# HB-UNI-SEN-PHO.net
KiCad netlist of a schematic drawn in EAGLE
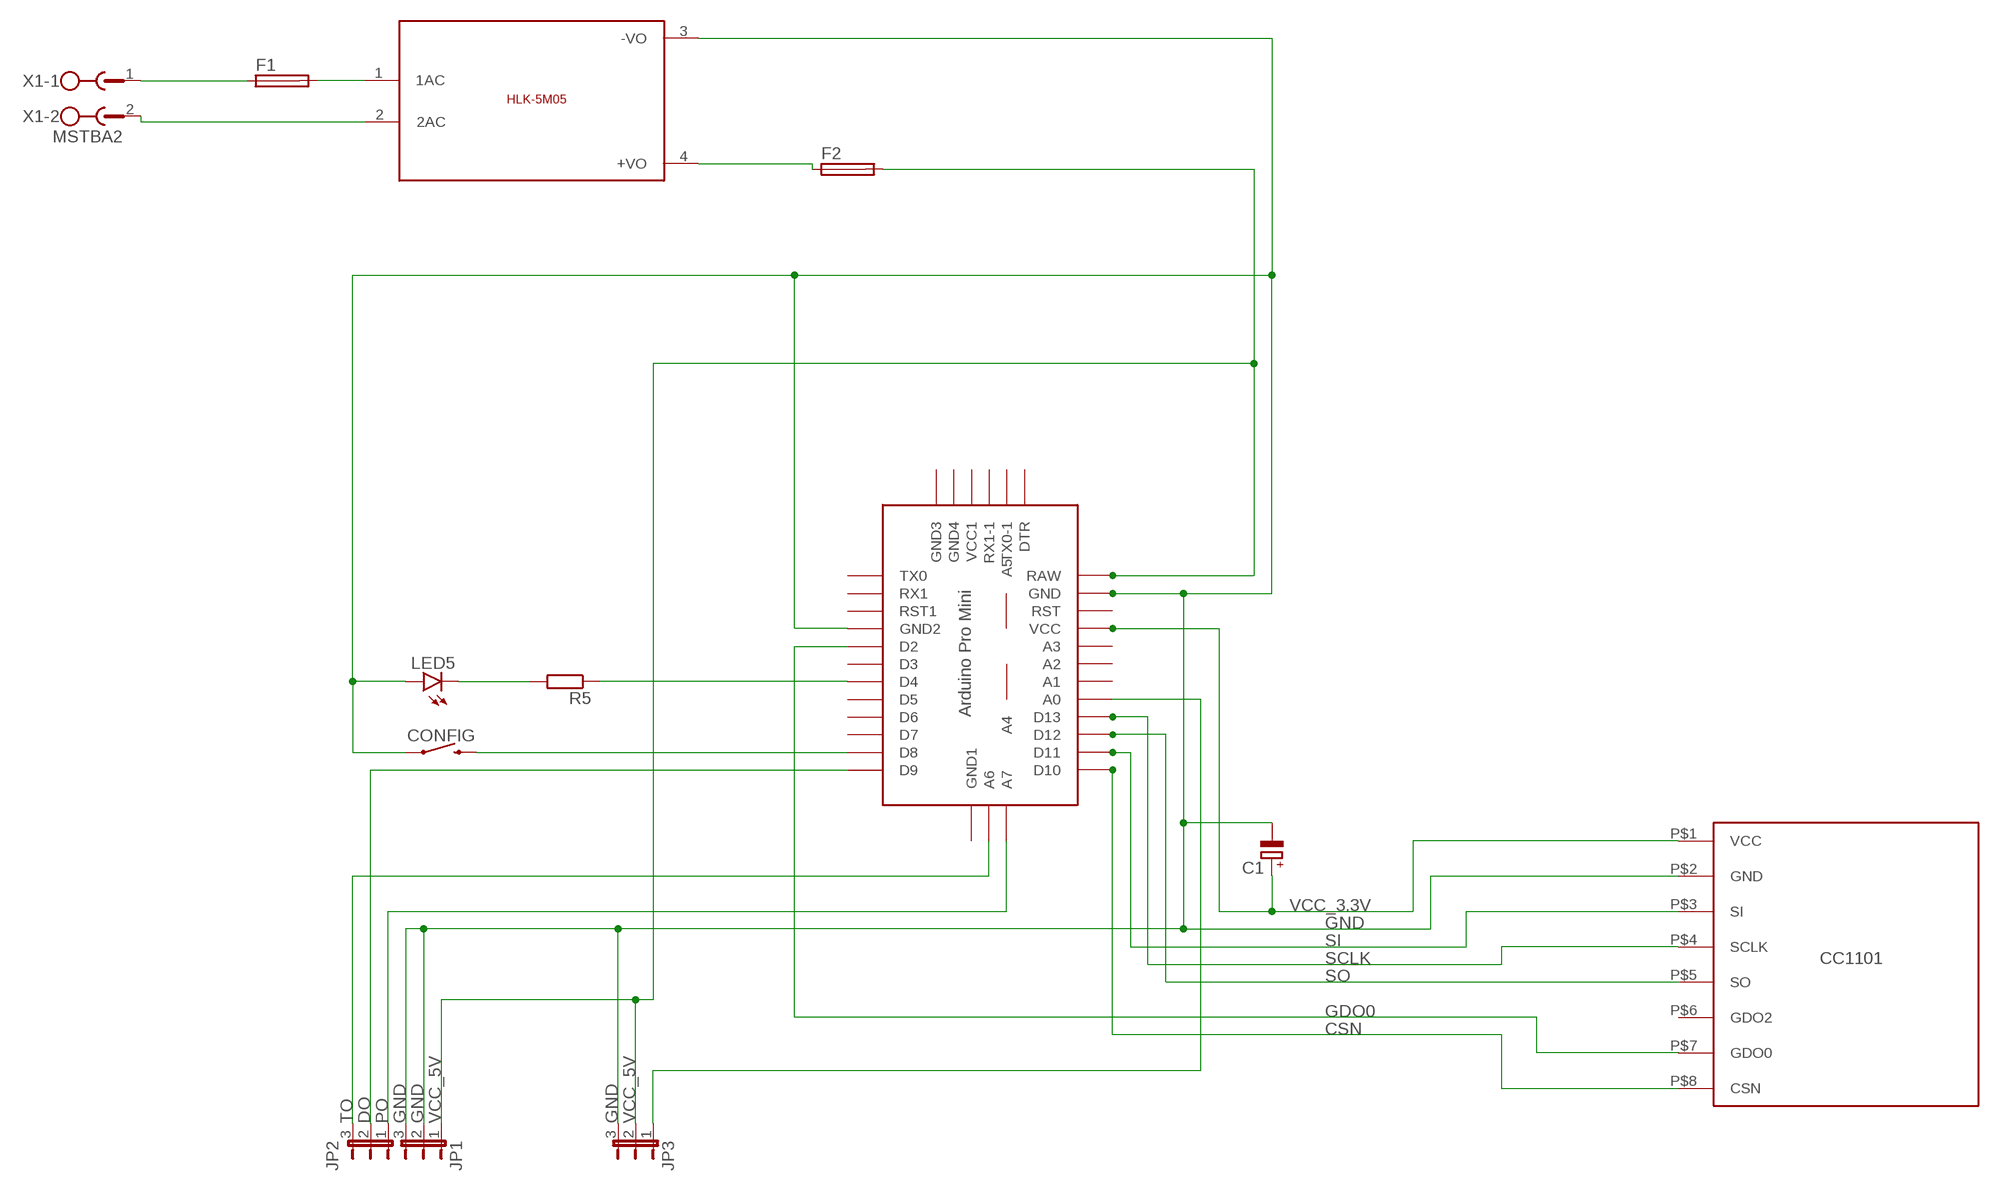
[diagram p0: schematic, sheet 1]

(export (version "E")
  (design (tool "Eeschema 10.0.6"))
  (components
    (comp (ref "C1")
      (value "CPOL-EUE2.5-5")
      (footprint "eagle-import:E2,5-5")
      (libsource (lib "eagle-import") (part "CPOL-EUE2.5-5"))
    )
    (comp (ref "CONFIG")
      (value "MOMENTARY-SWITCH-SPST-PTH-6.0MM-KIT")
      (footprint "eagle-import:TACTILE_SWITCH_PTH_6.0MM_KIT")
      (libsource (lib "eagle-import") (part "MOMENTARY-SWITCH-SPST-PTH-6.0MM-KIT"))
    )
    (comp (ref "F1")
      (value "SH22,5A")
      (footprint "eagle-import:SH22,5A")
      (fields (field (name "MPN") "0031.7701.11"))
      (libsource (lib "eagle-import") (part "SH22,5A"))
    )
    (comp (ref "F2")
      (value "SH22,5A")
      (footprint "eagle-import:SH22,5A")
      (fields (field (name "MPN") "0031.7701.11"))
      (libsource (lib "eagle-import") (part "SH22,5A"))
    )
    (comp (ref "JP1")
      (value "JP2E")
      (footprint "eagle-import:JP2")
      (libsource (lib "eagle-import") (part "JP2E"))
    )
    (comp (ref "JP2")
      (value "JP2E")
      (footprint "eagle-import:JP2")
      (libsource (lib "eagle-import") (part "JP2E"))
    )
    (comp (ref "JP3")
      (value "JP2E")
      (footprint "eagle-import:JP2")
      (libsource (lib "eagle-import") (part "JP2E"))
    )
    (comp (ref "LED5")
      (value "LED3MM")
      (footprint "eagle-import:LED3MM")
      (libsource (lib "eagle-import") (part "LED3MM"))
    )
    (comp (ref "R5")
      (value "R-EU_0309/10")
      (footprint "eagle-import:0309_10")
      (libsource (lib "eagle-import") (part "R-EU_0309/10"))
    )
    (comp (ref "U$2")
      (value "ABK-PRO-MINI")
      (footprint "eagle-import:ABK-PRO-MINI")
      (libsource (lib "eagle-import") (part "ABK-PRO-MINI"))
    )
    (comp (ref "U$3")
      (value "5VDC/5W")
      (footprint "eagle-import:HLK-5M05")
      (libsource (lib "eagle-import") (part "HLK-5M05"))
    )
    (comp (ref "U$4")
      (value "CC1101")
      (footprint "eagle-import:CC1101")
      (libsource (lib "eagle-import") (part "CC1101"))
    )
    (comp (ref "X1")
      (value "MSTBA2")
      (footprint "eagle-import:MSTBA2")
      (fields (field (name "MF") "FARNELL") (field (name "MPN") "1757242"))
      (libsource (lib "eagle-import") (part "MSTBA2"))
    )
  )
  (nets
    (net (code "1") (name "/CSN") (class "Default")
      (node (ref "U$2") (pin "D10") (pinfunction "D10_D10") (pintype "bidirectional"))
      (node (ref "U$4") (pin "P$8") (pinfunction "CSN_P$8") (pintype "bidirectional"))
    )
    (net (code "2") (name "/DO") (class "Default")
      (node (ref "JP2") (pin "2") (pinfunction "2_2") (pintype "passive"))
      (node (ref "U$2") (pin "D9") (pinfunction "D9_D9") (pintype "bidirectional"))
    )
    (net (code "3") (name "/GDO0") (class "Default")
      (node (ref "U$2") (pin "D2") (pinfunction "D2_D2") (pintype "bidirectional"))
      (node (ref "U$4") (pin "P$7") (pinfunction "GDO0_P$7") (pintype "bidirectional"))
    )
    (net (code "4") (name "/GND") (class "Default")
      (node (ref "C1") (pin "-") (pinfunction "-_-") (pintype "passive"))
      (node (ref "CONFIG") (pin "1") (pinfunction "1_1") (pintype "passive"))
      (node (ref "JP1") (pin "2") (pinfunction "2_2") (pintype "passive"))
      (node (ref "JP1") (pin "3") (pinfunction "3_3") (pintype "passive"))
      (node (ref "JP3") (pin "3") (pinfunction "3_3") (pintype "passive"))
      (node (ref "LED5") (pin "A") (pinfunction "A_A") (pintype "passive"))
      (node (ref "U$2") (pin "GND") (pinfunction "GND_GND") (pintype "bidirectional"))
      (node (ref "U$2") (pin "GND1") (pinfunction "GND2_GND1") (pintype "bidirectional"))
      (node (ref "U$3") (pin "3") (pinfunction "-VO_3") (pintype "bidirectional"))
      (node (ref "U$4") (pin "P$2") (pinfunction "GND_P$2") (pintype "bidirectional"))
    )
    (net (code "5") (name "/PO") (class "Default")
      (node (ref "JP2") (pin "1") (pinfunction "1_1") (pintype "passive"))
      (node (ref "U$2") (pin "A7") (pinfunction "A7_A7") (pintype "bidirectional"))
    )
    (net (code "6") (name "/SCLK") (class "Default")
      (node (ref "U$2") (pin "D13") (pinfunction "D13_D13") (pintype "bidirectional"))
      (node (ref "U$4") (pin "P$4") (pinfunction "SCLK_P$4") (pintype "bidirectional"))
    )
    (net (code "7") (name "/SI") (class "Default")
      (node (ref "U$2") (pin "D11") (pinfunction "D11_D11") (pintype "bidirectional"))
      (node (ref "U$4") (pin "P$3") (pinfunction "SI_P$3") (pintype "bidirectional"))
    )
    (net (code "8") (name "/SO") (class "Default")
      (node (ref "U$2") (pin "D12") (pinfunction "D12_D12") (pintype "bidirectional"))
      (node (ref "U$4") (pin "P$5") (pinfunction "SO_P$5") (pintype "bidirectional"))
    )
    (net (code "9") (name "/TO") (class "Default")
      (node (ref "JP2") (pin "3") (pinfunction "3_3") (pintype "passive"))
      (node (ref "U$2") (pin "A6") (pinfunction "A6_A6") (pintype "bidirectional"))
    )
    (net (code "10") (name "/VCC_3.3V") (class "Default")
      (node (ref "C1") (pin "+") (pinfunction "+_+") (pintype "passive"))
      (node (ref "U$2") (pin "VCC") (pinfunction "VCC_VCC") (pintype "bidirectional"))
      (node (ref "U$4") (pin "P$1") (pinfunction "VCC_P$1") (pintype "bidirectional"))
    )
    (net (code "11") (name "/VCC_5V") (class "Default")
      (node (ref "F2") (pin "2") (pinfunction "2_2") (pintype "passive"))
      (node (ref "JP1") (pin "1") (pinfunction "1_1") (pintype "passive"))
      (node (ref "JP3") (pin "2") (pinfunction "2_2") (pintype "passive"))
      (node (ref "U$2") (pin "RAW") (pinfunction "RAW_RAW") (pintype "bidirectional"))
    )
    (net (code "12") (name "Net-(CONFIG-2)") (class "Default")
      (node (ref "CONFIG") (pin "3") (pinfunction "2_3") (pintype "passive"))
      (node (ref "U$2") (pin "D8") (pinfunction "D8_D8") (pintype "bidirectional"))
    )
    (net (code "13") (name "Net-(F1-Pad1)") (class "Default")
      (node (ref "F1") (pin "1") (pinfunction "1_1") (pintype "passive"))
      (node (ref "X1") (pin "1") (pinfunction "1_1") (pintype "passive"))
    )
    (net (code "14") (name "Net-(JP3-Pad1)") (class "Default")
      (node (ref "JP3") (pin "1") (pinfunction "1_1") (pintype "passive"))
      (node (ref "U$2") (pin "A0") (pinfunction "A0_A0") (pintype "bidirectional"))
    )
    (net (code "15") (name "Net-(LED5-C)") (class "Default")
      (node (ref "LED5") (pin "K") (pinfunction "C_K") (pintype "passive"))
      (node (ref "R5") (pin "2") (pinfunction "2_2") (pintype "passive"))
    )
    (net (code "16") (name "Net-(R5-Pad1)") (class "Default")
      (node (ref "R5") (pin "1") (pinfunction "1_1") (pintype "passive"))
      (node (ref "U$2") (pin "D4") (pinfunction "D4_D4") (pintype "bidirectional"))
    )
    (net (code "17") (name "Net-(U$3-+VO)") (class "Default")
      (node (ref "F2") (pin "1") (pinfunction "1_1") (pintype "passive"))
      (node (ref "U$3") (pin "4") (pinfunction "+VO_4") (pintype "bidirectional"))
    )
    (net (code "18") (name "Net-(U$3-1AC)") (class "Default")
      (node (ref "F1") (pin "2") (pinfunction "2_2") (pintype "passive"))
      (node (ref "U$3") (pin "1") (pinfunction "1AC_1") (pintype "bidirectional"))
    )
    (net (code "19") (name "Net-(U$3-2AC)") (class "Default")
      (node (ref "U$3") (pin "2") (pinfunction "2AC_2") (pintype "bidirectional"))
      (node (ref "X1") (pin "2") (pinfunction "1_2") (pintype "passive"))
    )
    (net (code "20") (name "unconnected-(U$2-GND1-PadGND4)") (class "Default")
      (node (ref "U$2") (pin "GND4") (pinfunction "GND1_GND4") (pintype "bidirectional"))
    )
    (net (code "21") (name "unconnected-(U$2-GND3-PadGND2)") (class "Default")
      (node (ref "U$2") (pin "GND2") (pinfunction "GND3_GND2") (pintype "bidirectional"))
    )
    (net (code "22") (name "unconnected-(U$2-GND4-PadGND3)") (class "Default")
      (node (ref "U$2") (pin "GND3") (pinfunction "GND4_GND3") (pintype "bidirectional"))
    )
    (net (code "23") (name "unconnected-(U$2-PadA1)") (class "Default")
      (node (ref "U$2") (pin "A1") (pinfunction "A1_A1") (pintype "bidirectional"))
    )
    (net (code "24") (name "unconnected-(U$2-PadA2)") (class "Default")
      (node (ref "U$2") (pin "A2") (pinfunction "A2_A2") (pintype "bidirectional"))
    )
    (net (code "25") (name "unconnected-(U$2-PadA3)") (class "Default")
      (node (ref "U$2") (pin "A3") (pinfunction "A3_A3") (pintype "bidirectional"))
    )
    (net (code "26") (name "unconnected-(U$2-PadA4)") (class "Default")
      (node (ref "U$2") (pin "A4") (pinfunction "A4_A4") (pintype "bidirectional"))
    )
    (net (code "27") (name "unconnected-(U$2-PadA5)") (class "Default")
      (node (ref "U$2") (pin "A5") (pinfunction "A5_A5") (pintype "bidirectional"))
    )
    (net (code "28") (name "unconnected-(U$2-PadD3)") (class "Default")
      (node (ref "U$2") (pin "D3") (pinfunction "D3_D3") (pintype "bidirectional"))
    )
    (net (code "29") (name "unconnected-(U$2-PadD5)") (class "Default")
      (node (ref "U$2") (pin "D5") (pinfunction "D5_D5") (pintype "bidirectional"))
    )
    (net (code "30") (name "unconnected-(U$2-PadD6)") (class "Default")
      (node (ref "U$2") (pin "D6") (pinfunction "D6_D6") (pintype "bidirectional"))
    )
    (net (code "31") (name "unconnected-(U$2-PadD7)") (class "Default")
      (node (ref "U$2") (pin "D7") (pinfunction "D7_D7") (pintype "bidirectional"))
    )
    (net (code "32") (name "unconnected-(U$2-PadDTR)") (class "Default")
      (node (ref "U$2") (pin "DTR") (pinfunction "DTR_DTR") (pintype "bidirectional"))
    )
    (net (code "33") (name "unconnected-(U$2-PadRST)") (class "Default")
      (node (ref "U$2") (pin "RST") (pinfunction "RST_RST") (pintype "bidirectional"))
    )
    (net (code "34") (name "unconnected-(U$2-PadRST1)") (class "Default")
      (node (ref "U$2") (pin "RST1") (pinfunction "RST1_RST1") (pintype "bidirectional"))
    )
    (net (code "35") (name "unconnected-(U$2-PadRX1)") (class "Default")
      (node (ref "U$2") (pin "RX1") (pinfunction "RX1_RX1") (pintype "bidirectional"))
    )
    (net (code "36") (name "unconnected-(U$2-PadRX1-1)") (class "Default")
      (node (ref "U$2") (pin "RX1-1") (pinfunction "RX1-1_RX1-1") (pintype "bidirectional"))
    )
    (net (code "37") (name "unconnected-(U$2-PadTX0)") (class "Default")
      (node (ref "U$2") (pin "TX0") (pinfunction "TX0_TX0") (pintype "bidirectional"))
    )
    (net (code "38") (name "unconnected-(U$2-PadTX0-1)") (class "Default")
      (node (ref "U$2") (pin "TX0-1") (pinfunction "TX0-1_TX0-1") (pintype "bidirectional"))
    )
    (net (code "39") (name "unconnected-(U$2-PadVCC1)") (class "Default")
      (node (ref "U$2") (pin "VCC1") (pinfunction "VCC1_VCC1") (pintype "bidirectional"))
    )
    (net (code "40") (name "unconnected-(U$4-GDO2-PadP$6)") (class "Default")
      (node (ref "U$4") (pin "P$6") (pinfunction "GDO2_P$6") (pintype "bidirectional"))
    )
  )
)
